# chaves.net
KiCad netlist of a schematic drawn in Altium Designer
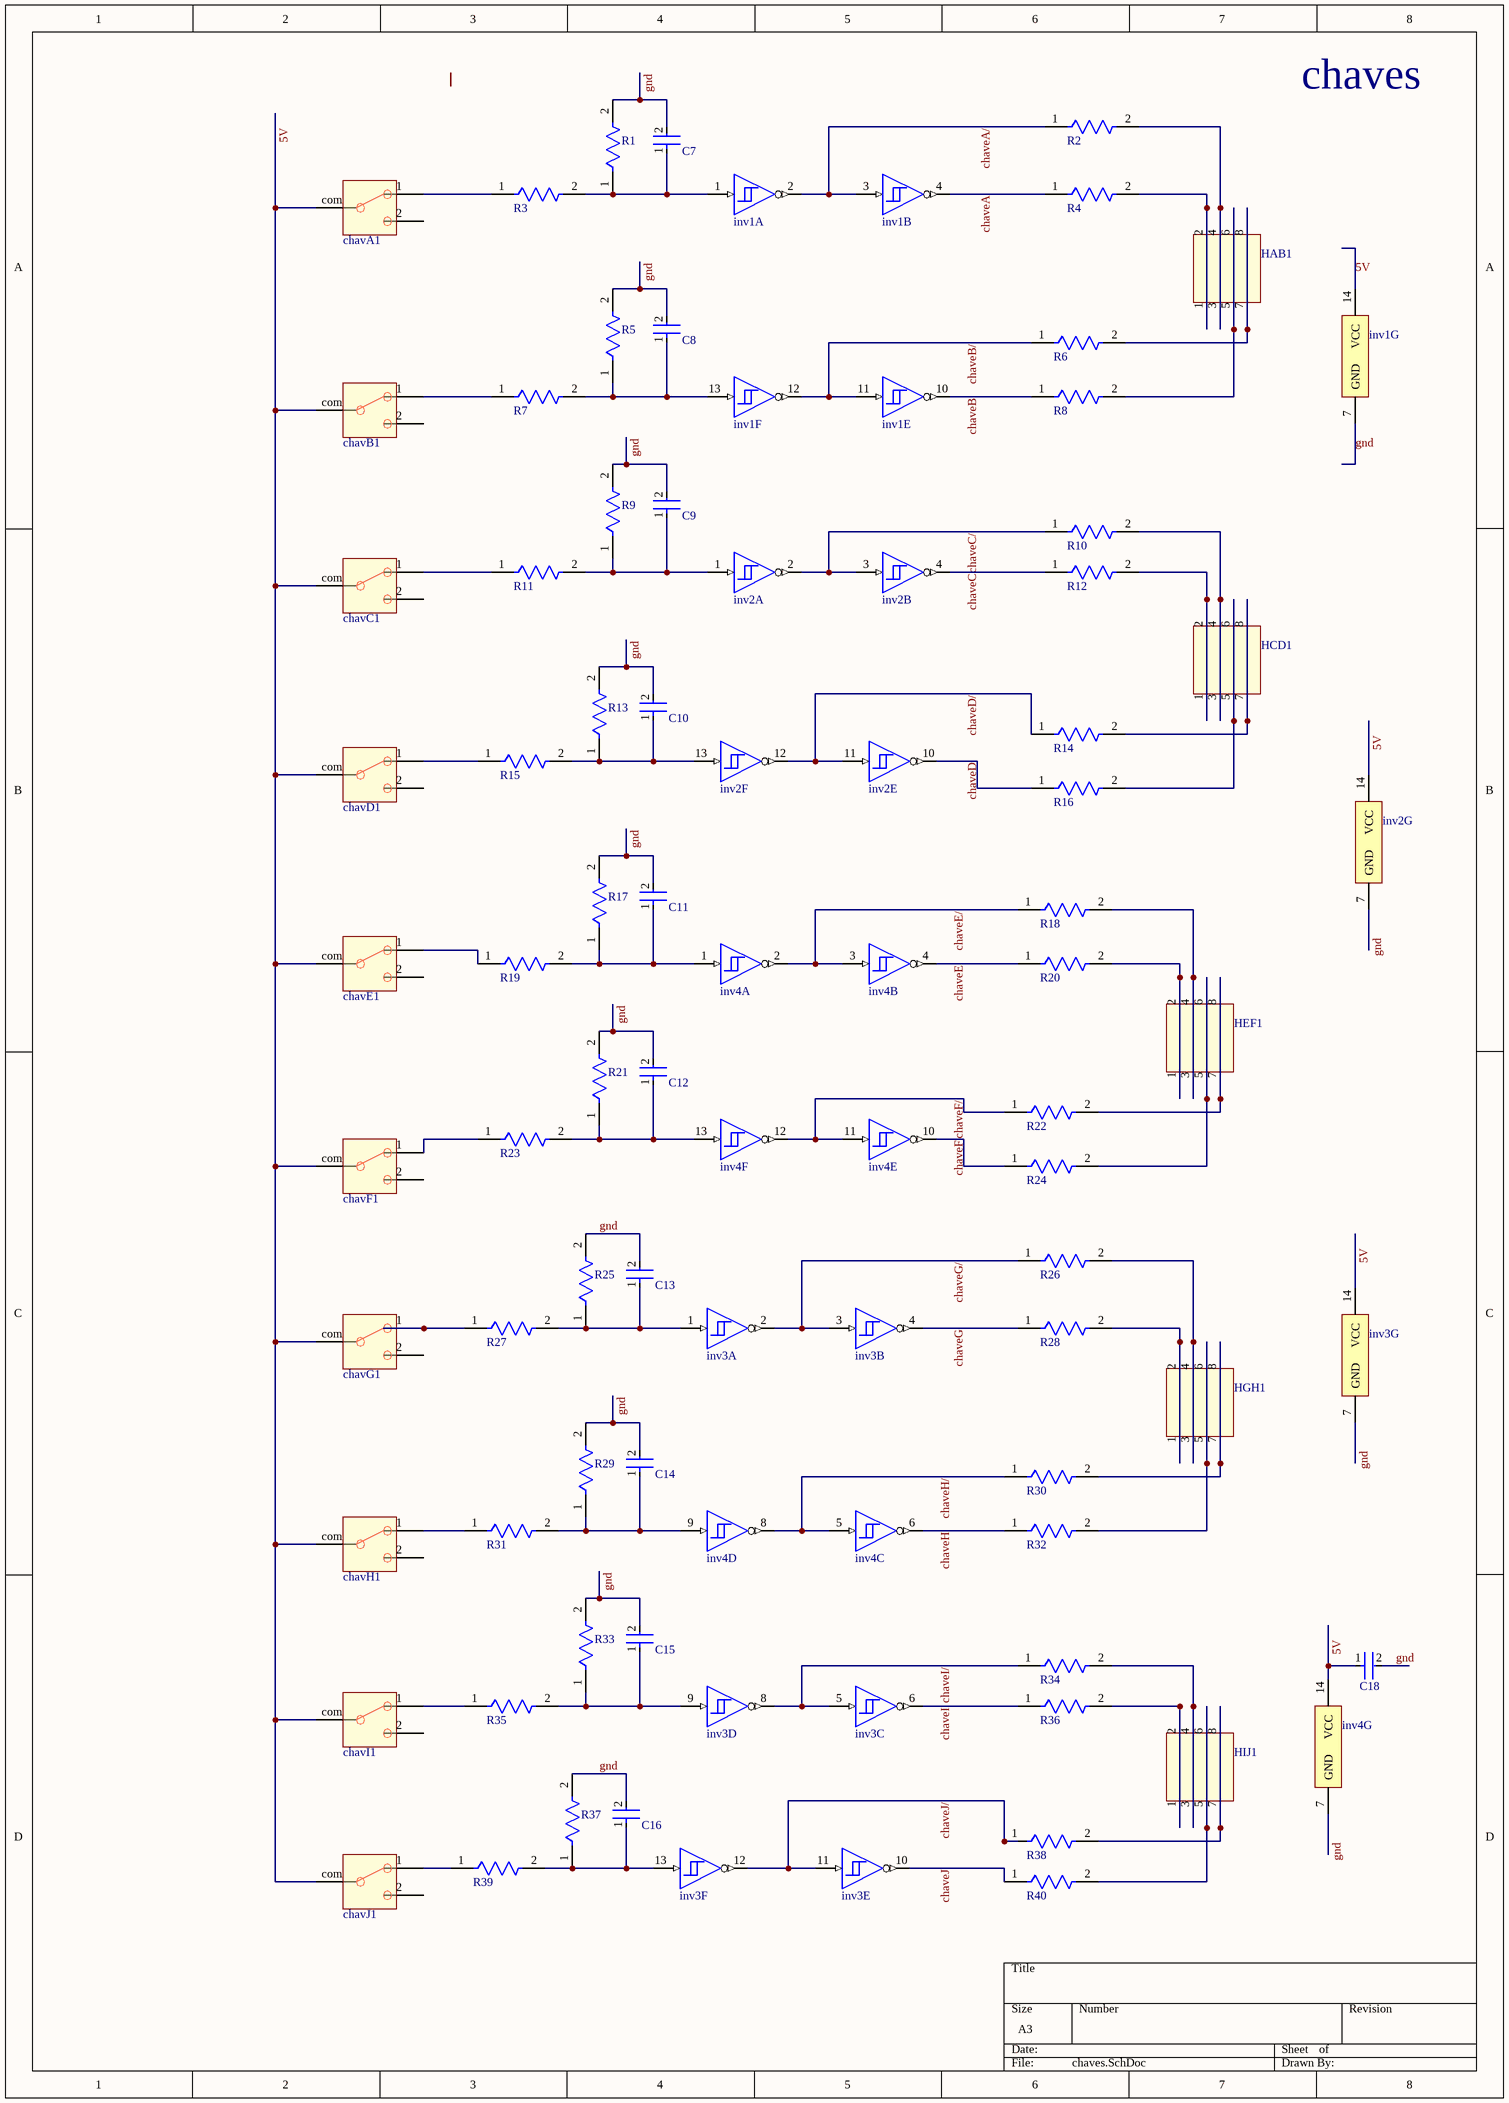
[diagram p0: chaves.SchDoc]

(export (version "E")
  (design (tool "Eeschema 10.0.6"))
  (components
    (comp (ref "C7")
      (value "RCER71H335K3K1H03B")
      (footprint "FP-RCE3M1-MFG")
      (description "Cap Ceramic 3.3uF 50V X7R ±10% Radial 5mm +125°C Automotive Ammo Pack")
      (fields (field (name "TOLERANCE") "10%"))
      (libsource (lib "Altium Content Vault") (part "02cd4be3c70576c341d710602a673aa"))
    )
    (comp (ref "C8")
      (value "RCER71H335K3K1H03B")
      (footprint "FP-RCE3M1-MFG")
      (description "Cap Ceramic 3.3uF 50V X7R ±10% Radial 5mm +125°C Automotive Ammo Pack")
      (fields (field (name "TOLERANCE") "10%"))
      (libsource (lib "Altium Content Vault") (part "02cd4be3c70576c341d710602a673aa"))
    )
    (comp (ref "C9")
      (value "RCER71H335K3K1H03B")
      (footprint "FP-RCE3M1-MFG")
      (description "Cap Ceramic 3.3uF 50V X7R ±10% Radial 5mm +125°C Automotive Ammo Pack")
      (fields (field (name "TOLERANCE") "10%"))
      (libsource (lib "Altium Content Vault") (part "02cd4be3c70576c341d710602a673aa"))
    )
    (comp (ref "C10")
      (value "RCER71H335K3K1H03B")
      (footprint "FP-RCE3M1-MFG")
      (description "Cap Ceramic 3.3uF 50V X7R ±10% Radial 5mm +125°C Automotive Ammo Pack")
      (fields (field (name "TOLERANCE") "10%"))
      (libsource (lib "Altium Content Vault") (part "02cd4be3c70576c341d710602a673aa"))
    )
    (comp (ref "C11")
      (value "RCER71H335K3K1H03B")
      (footprint "FP-RCE3M1-MFG")
      (description "Cap Ceramic 3.3uF 50V X7R ±10% Radial 5mm +125°C Automotive Ammo Pack")
      (fields (field (name "TOLERANCE") "10%"))
      (libsource (lib "Altium Content Vault") (part "02cd4be3c70576c341d710602a673aa"))
    )
    (comp (ref "C12")
      (value "RCER71H335K3K1H03B")
      (footprint "FP-RCE3M1-MFG")
      (description "Cap Ceramic 3.3uF 50V X7R ±10% Radial 5mm +125°C Automotive Ammo Pack")
      (fields (field (name "TOLERANCE") "10%"))
      (libsource (lib "Altium Content Vault") (part "02cd4be3c70576c341d710602a673aa"))
    )
    (comp (ref "C13")
      (value "RCER71H335K3K1H03B")
      (footprint "FP-RCE3M1-MFG")
      (description "Cap Ceramic 3.3uF 50V X7R ±10% Radial 5mm +125°C Automotive Ammo Pack")
      (fields (field (name "TOLERANCE") "10%"))
      (libsource (lib "Altium Content Vault") (part "02cd4be3c70576c341d710602a673aa"))
    )
    (comp (ref "C14")
      (value "RCER71H335K3K1H03B")
      (footprint "FP-RCE3M1-MFG")
      (description "Cap Ceramic 3.3uF 50V X7R ±10% Radial 5mm +125°C Automotive Ammo Pack")
      (fields (field (name "TOLERANCE") "10%"))
      (libsource (lib "Altium Content Vault") (part "02cd4be3c70576c341d710602a673aa"))
    )
    (comp (ref "C15")
      (value "RCER71H335K3K1H03B")
      (footprint "FP-RCE3M1-MFG")
      (description "Cap Ceramic 3.3uF 50V X7R ±10% Radial 5mm +125°C Automotive Ammo Pack")
      (fields (field (name "TOLERANCE") "10%"))
      (libsource (lib "Altium Content Vault") (part "02cd4be3c70576c341d710602a673aa"))
    )
    (comp (ref "C16")
      (value "RCER71H335K3K1H03B")
      (footprint "FP-RCE3M1-MFG")
      (description "Cap Ceramic 3.3uF 50V X7R ±10% Radial 5mm +125°C Automotive Ammo Pack")
      (fields (field (name "TOLERANCE") "10%"))
      (libsource (lib "Altium Content Vault") (part "02cd4be3c70576c341d710602a673aa"))
    )
    (comp (ref "C18")
      (value "RCER71H335K3K1H03B")
      (footprint "FP-RCE3M1-MFG")
      (description "Cap Ceramic 3.3uF 50V X7R ±10% Radial 5mm +125°C Automotive Ammo Pack")
      (fields (field (name "TOLERANCE") "10%"))
      (libsource (lib "Altium Content Vault") (part "02cd4be3c70576c341d710602a673aa"))
    )
    (comp (ref "chavA1")
      (value "chave MTS-102")
      (footprint "MTS-102")
      (description "chave caso seja usadsada sendo encaixada")
      (libsource (lib "Schlib1") (part "MTS-102"))
    )
    (comp (ref "chavB1")
      (value "chave MTS-102")
      (footprint "MTS-102")
      (description "chave caso seja usadsada sendo encaixada")
      (libsource (lib "Schlib1") (part "MTS-102"))
    )
    (comp (ref "chavC1")
      (value "chave MTS-102")
      (footprint "MTS-102")
      (description "chave caso seja usadsada sendo encaixada")
      (libsource (lib "Schlib1") (part "MTS-102"))
    )
    (comp (ref "chavD1")
      (value "chave MTS-102")
      (footprint "MTS-102")
      (description "chave caso seja usadsada sendo encaixada")
      (libsource (lib "Schlib1") (part "MTS-102"))
    )
    (comp (ref "chavE1")
      (value "chave MTS-102")
      (footprint "MTS-102")
      (description "chave caso seja usadsada sendo encaixada")
      (libsource (lib "Schlib1") (part "MTS-102"))
    )
    (comp (ref "chavF1")
      (value "chave MTS-102")
      (footprint "MTS-102")
      (description "chave caso seja usadsada sendo encaixada")
      (libsource (lib "Schlib1") (part "MTS-102"))
    )
    (comp (ref "chavG1")
      (value "chave MTS-102")
      (footprint "MTS-102")
      (description "chave caso seja usadsada sendo encaixada")
      (libsource (lib "Schlib1") (part "MTS-102"))
    )
    (comp (ref "chavH1")
      (value "chave MTS-102")
      (footprint "MTS-102")
      (description "chave caso seja usadsada sendo encaixada")
      (libsource (lib "Schlib1") (part "MTS-102"))
    )
    (comp (ref "chavI1")
      (value "chave MTS-102")
      (footprint "MTS-102")
      (description "chave caso seja usadsada sendo encaixada")
      (libsource (lib "Schlib1") (part "MTS-102"))
    )
    (comp (ref "chavJ1")
      (value "chave MTS-102")
      (footprint "MTS-102")
      (description "chave caso seja usadsada sendo encaixada")
      (libsource (lib "Schlib1") (part "MTS-102"))
    )
    (comp (ref "HAB1")
      (value "header 2x4")
      (footprint "header 2x4")
      (description "header male 2x4")
      (libsource (lib "Schlib1") (part "header 2x4"))
    )
    (comp (ref "HCD1")
      (value "header 2x4")
      (footprint "header 2x4")
      (description "header male 2x4")
      (libsource (lib "Schlib1") (part "header 2x4"))
    )
    (comp (ref "HEF1")
      (value "header 2x4")
      (footprint "header 2x4")
      (description "header male 2x4")
      (libsource (lib "Schlib1") (part "header 2x4"))
    )
    (comp (ref "HGH1")
      (value "header 2x4")
      (footprint "header 2x4")
      (description "header male 2x4")
      (libsource (lib "Schlib1") (part "header 2x4"))
    )
    (comp (ref "HIJ1")
      (value "header 2x4")
      (footprint "header 2x4")
      (description "header male 2x4")
      (libsource (lib "Schlib1") (part "header 2x4"))
    )
    (comp (ref "inv1")
      (value "SN74HC14N")
      (footprint "N0014A")
      (description "Hex Schmitt-Trigger Inverters, N0014A, TUBE")
      (fields
        (field (name "MANUFACTURER") "Texas Instruments")
        (field (name "GENERIC PART NUMBER") "SN74HC14")
      )
      (libsource (lib "Altium Content Vault") (part "TI-CD_SNX4XXXXXX4X_19A-14-SCHMITT"))
    )
    (comp (ref "inv2")
      (value "SN74HC14N")
      (footprint "N0014A")
      (description "Hex Schmitt-Trigger Inverters, N0014A, TUBE")
      (fields
        (field (name "MANUFACTURER") "Texas Instruments")
        (field (name "GENERIC PART NUMBER") "SN74HC14")
      )
      (libsource (lib "Altium Content Vault") (part "TI-CD_SNX4XXXXXX4X_19A-14-SCHMITT"))
    )
    (comp (ref "inv3")
      (value "SN74HC14N")
      (footprint "N0014A")
      (description "Hex Schmitt-Trigger Inverters, N0014A, TUBE")
      (fields
        (field (name "MANUFACTURER") "Texas Instruments")
        (field (name "GENERIC PART NUMBER") "SN74HC14")
      )
      (libsource (lib "Altium Content Vault") (part "TI-CD_SNX4XXXXXX4X_19A-14-SCHMITT"))
    )
    (comp (ref "inv4")
      (value "SN74HC14N")
      (footprint "N0014A")
      (description "Hex Schmitt-Trigger Inverters, N0014A, TUBE")
      (fields
        (field (name "MANUFACTURER") "Texas Instruments")
        (field (name "GENERIC PART NUMBER") "SN74HC14")
      )
      (libsource (lib "Altium Content Vault") (part "TI-CD_SNX4XXXXXX4X_19A-14-SCHMITT"))
    )
    (comp (ref "R1")
      (value "MRS16000C2002FCT00")
      (footprint "FP-MRS1600-MFG")
      (description "RES 20K OHM 0.4W 1% AXIAL")
      (fields (field (name "TOLERANCE") "1%"))
      (libsource (lib "Altium Content Vault") (part "1029c3af85768c4190bb7ad29bc67b5"))
    )
    (comp (ref "R2")
      (value "MRS16000C2002FCT00")
      (footprint "FP-MRS1600-MFG")
      (description "RES 20K OHM 0.4W 1% AXIAL")
      (fields (field (name "TOLERANCE") "1%"))
      (libsource (lib "Altium Content Vault") (part "1029c3af85768c4190bb7ad29bc67b5"))
    )
    (comp (ref "R3")
      (value "MRS16000C2002FCT00")
      (footprint "FP-MRS1600-MFG")
      (description "RES 20K OHM 0.4W 1% AXIAL")
      (fields (field (name "TOLERANCE") "1%"))
      (libsource (lib "Altium Content Vault") (part "1029c3af85768c4190bb7ad29bc67b5"))
    )
    (comp (ref "R4")
      (value "MRS16000C2002FCT00")
      (footprint "FP-MRS1600-MFG")
      (description "RES 20K OHM 0.4W 1% AXIAL")
      (fields (field (name "TOLERANCE") "1%"))
      (libsource (lib "Altium Content Vault") (part "1029c3af85768c4190bb7ad29bc67b5"))
    )
    (comp (ref "R5")
      (value "MRS16000C2002FCT00")
      (footprint "FP-MRS1600-MFG")
      (description "RES 20K OHM 0.4W 1% AXIAL")
      (fields (field (name "TOLERANCE") "1%"))
      (libsource (lib "Altium Content Vault") (part "1029c3af85768c4190bb7ad29bc67b5"))
    )
    (comp (ref "R6")
      (value "MRS16000C2002FCT00")
      (footprint "FP-MRS1600-MFG")
      (description "RES 20K OHM 0.4W 1% AXIAL")
      (fields (field (name "TOLERANCE") "1%"))
      (libsource (lib "Altium Content Vault") (part "1029c3af85768c4190bb7ad29bc67b5"))
    )
    (comp (ref "R7")
      (value "MRS16000C2002FCT00")
      (footprint "FP-MRS1600-MFG")
      (description "RES 20K OHM 0.4W 1% AXIAL")
      (fields (field (name "TOLERANCE") "1%"))
      (libsource (lib "Altium Content Vault") (part "1029c3af85768c4190bb7ad29bc67b5"))
    )
    (comp (ref "R8")
      (value "MRS16000C2002FCT00")
      (footprint "FP-MRS1600-MFG")
      (description "RES 20K OHM 0.4W 1% AXIAL")
      (fields (field (name "TOLERANCE") "1%"))
      (libsource (lib "Altium Content Vault") (part "1029c3af85768c4190bb7ad29bc67b5"))
    )
    (comp (ref "R9")
      (value "MRS16000C2002FCT00")
      (footprint "FP-MRS1600-MFG")
      (description "RES 20K OHM 0.4W 1% AXIAL")
      (fields (field (name "TOLERANCE") "1%"))
      (libsource (lib "Altium Content Vault") (part "1029c3af85768c4190bb7ad29bc67b5"))
    )
    (comp (ref "R10")
      (value "MRS16000C2002FCT00")
      (footprint "FP-MRS1600-MFG")
      (description "RES 20K OHM 0.4W 1% AXIAL")
      (fields (field (name "TOLERANCE") "1%"))
      (libsource (lib "Altium Content Vault") (part "1029c3af85768c4190bb7ad29bc67b5"))
    )
    (comp (ref "R11")
      (value "MRS16000C2002FCT00")
      (footprint "FP-MRS1600-MFG")
      (description "RES 20K OHM 0.4W 1% AXIAL")
      (fields (field (name "TOLERANCE") "1%"))
      (libsource (lib "Altium Content Vault") (part "1029c3af85768c4190bb7ad29bc67b5"))
    )
    (comp (ref "R12")
      (value "MRS16000C2002FCT00")
      (footprint "FP-MRS1600-MFG")
      (description "RES 20K OHM 0.4W 1% AXIAL")
      (fields (field (name "TOLERANCE") "1%"))
      (libsource (lib "Altium Content Vault") (part "1029c3af85768c4190bb7ad29bc67b5"))
    )
    (comp (ref "R13")
      (value "MRS16000C2002FCT00")
      (footprint "FP-MRS1600-MFG")
      (description "RES 20K OHM 0.4W 1% AXIAL")
      (fields (field (name "TOLERANCE") "1%"))
      (libsource (lib "Altium Content Vault") (part "1029c3af85768c4190bb7ad29bc67b5"))
    )
    (comp (ref "R14")
      (value "MRS16000C2002FCT00")
      (footprint "FP-MRS1600-MFG")
      (description "RES 20K OHM 0.4W 1% AXIAL")
      (fields (field (name "TOLERANCE") "1%"))
      (libsource (lib "Altium Content Vault") (part "1029c3af85768c4190bb7ad29bc67b5"))
    )
    (comp (ref "R15")
      (value "MRS16000C2002FCT00")
      (footprint "FP-MRS1600-MFG")
      (description "RES 20K OHM 0.4W 1% AXIAL")
      (fields (field (name "TOLERANCE") "1%"))
      (libsource (lib "Altium Content Vault") (part "1029c3af85768c4190bb7ad29bc67b5"))
    )
    (comp (ref "R16")
      (value "MRS16000C2002FCT00")
      (footprint "FP-MRS1600-MFG")
      (description "RES 20K OHM 0.4W 1% AXIAL")
      (fields (field (name "TOLERANCE") "1%"))
      (libsource (lib "Altium Content Vault") (part "1029c3af85768c4190bb7ad29bc67b5"))
    )
    (comp (ref "R17")
      (value "MRS16000C2002FCT00")
      (footprint "FP-MRS1600-MFG")
      (description "RES 20K OHM 0.4W 1% AXIAL")
      (fields (field (name "TOLERANCE") "1%"))
      (libsource (lib "Altium Content Vault") (part "1029c3af85768c4190bb7ad29bc67b5"))
    )
    (comp (ref "R18")
      (value "MRS16000C2002FCT00")
      (footprint "FP-MRS1600-MFG")
      (description "RES 20K OHM 0.4W 1% AXIAL")
      (fields (field (name "TOLERANCE") "1%"))
      (libsource (lib "Altium Content Vault") (part "1029c3af85768c4190bb7ad29bc67b5"))
    )
    (comp (ref "R19")
      (value "MRS16000C2002FCT00")
      (footprint "FP-MRS1600-MFG")
      (description "RES 20K OHM 0.4W 1% AXIAL")
      (fields (field (name "TOLERANCE") "1%"))
      (libsource (lib "Altium Content Vault") (part "1029c3af85768c4190bb7ad29bc67b5"))
    )
    (comp (ref "R20")
      (value "MRS16000C2002FCT00")
      (footprint "FP-MRS1600-MFG")
      (description "RES 20K OHM 0.4W 1% AXIAL")
      (fields (field (name "TOLERANCE") "1%"))
      (libsource (lib "Altium Content Vault") (part "1029c3af85768c4190bb7ad29bc67b5"))
    )
    (comp (ref "R21")
      (value "MRS16000C2002FCT00")
      (footprint "FP-MRS1600-MFG")
      (description "RES 20K OHM 0.4W 1% AXIAL")
      (fields (field (name "TOLERANCE") "1%"))
      (libsource (lib "Altium Content Vault") (part "1029c3af85768c4190bb7ad29bc67b5"))
    )
    (comp (ref "R22")
      (value "MRS16000C2002FCT00")
      (footprint "FP-MRS1600-MFG")
      (description "RES 20K OHM 0.4W 1% AXIAL")
      (fields (field (name "TOLERANCE") "1%"))
      (libsource (lib "Altium Content Vault") (part "1029c3af85768c4190bb7ad29bc67b5"))
    )
    (comp (ref "R23")
      (value "MRS16000C2002FCT00")
      (footprint "FP-MRS1600-MFG")
      (description "RES 20K OHM 0.4W 1% AXIAL")
      (fields (field (name "TOLERANCE") "1%"))
      (libsource (lib "Altium Content Vault") (part "1029c3af85768c4190bb7ad29bc67b5"))
    )
    (comp (ref "R24")
      (value "MRS16000C2002FCT00")
      (footprint "FP-MRS1600-MFG")
      (description "RES 20K OHM 0.4W 1% AXIAL")
      (fields (field (name "TOLERANCE") "1%"))
      (libsource (lib "Altium Content Vault") (part "1029c3af85768c4190bb7ad29bc67b5"))
    )
    (comp (ref "R25")
      (value "MRS16000C2002FCT00")
      (footprint "FP-MRS1600-MFG")
      (description "RES 20K OHM 0.4W 1% AXIAL")
      (fields (field (name "TOLERANCE") "1%"))
      (libsource (lib "Altium Content Vault") (part "1029c3af85768c4190bb7ad29bc67b5"))
    )
    (comp (ref "R26")
      (value "MRS16000C2002FCT00")
      (footprint "FP-MRS1600-MFG")
      (description "RES 20K OHM 0.4W 1% AXIAL")
      (fields (field (name "TOLERANCE") "1%"))
      (libsource (lib "Altium Content Vault") (part "1029c3af85768c4190bb7ad29bc67b5"))
    )
    (comp (ref "R27")
      (value "MRS16000C2002FCT00")
      (footprint "FP-MRS1600-MFG")
      (description "RES 20K OHM 0.4W 1% AXIAL")
      (fields (field (name "TOLERANCE") "1%"))
      (libsource (lib "Altium Content Vault") (part "1029c3af85768c4190bb7ad29bc67b5"))
    )
    (comp (ref "R28")
      (value "MRS16000C2002FCT00")
      (footprint "FP-MRS1600-MFG")
      (description "RES 20K OHM 0.4W 1% AXIAL")
      (fields (field (name "TOLERANCE") "1%"))
      (libsource (lib "Altium Content Vault") (part "1029c3af85768c4190bb7ad29bc67b5"))
    )
    (comp (ref "R29")
      (value "MRS16000C2002FCT00")
      (footprint "FP-MRS1600-MFG")
      (description "RES 20K OHM 0.4W 1% AXIAL")
      (fields (field (name "TOLERANCE") "1%"))
      (libsource (lib "Altium Content Vault") (part "1029c3af85768c4190bb7ad29bc67b5"))
    )
    (comp (ref "R30")
      (value "MRS16000C2002FCT00")
      (footprint "FP-MRS1600-MFG")
      (description "RES 20K OHM 0.4W 1% AXIAL")
      (fields (field (name "TOLERANCE") "1%"))
      (libsource (lib "Altium Content Vault") (part "1029c3af85768c4190bb7ad29bc67b5"))
    )
    (comp (ref "R31")
      (value "MRS16000C2002FCT00")
      (footprint "FP-MRS1600-MFG")
      (description "RES 20K OHM 0.4W 1% AXIAL")
      (fields (field (name "TOLERANCE") "1%"))
      (libsource (lib "Altium Content Vault") (part "1029c3af85768c4190bb7ad29bc67b5"))
    )
    (comp (ref "R32")
      (value "MRS16000C2002FCT00")
      (footprint "FP-MRS1600-MFG")
      (description "RES 20K OHM 0.4W 1% AXIAL")
      (fields (field (name "TOLERANCE") "1%"))
      (libsource (lib "Altium Content Vault") (part "1029c3af85768c4190bb7ad29bc67b5"))
    )
    (comp (ref "R33")
      (value "MRS16000C2002FCT00")
      (footprint "FP-MRS1600-MFG")
      (description "RES 20K OHM 0.4W 1% AXIAL")
      (fields (field (name "TOLERANCE") "1%"))
      (libsource (lib "Altium Content Vault") (part "1029c3af85768c4190bb7ad29bc67b5"))
    )
    (comp (ref "R34")
      (value "MRS16000C2002FCT00")
      (footprint "FP-MRS1600-MFG")
      (description "RES 20K OHM 0.4W 1% AXIAL")
      (fields (field (name "TOLERANCE") "1%"))
      (libsource (lib "Altium Content Vault") (part "1029c3af85768c4190bb7ad29bc67b5"))
    )
    (comp (ref "R35")
      (value "MRS16000C2002FCT00")
      (footprint "FP-MRS1600-MFG")
      (description "RES 20K OHM 0.4W 1% AXIAL")
      (fields (field (name "TOLERANCE") "1%"))
      (libsource (lib "Altium Content Vault") (part "1029c3af85768c4190bb7ad29bc67b5"))
    )
    (comp (ref "R36")
      (value "MRS16000C2002FCT00")
      (footprint "FP-MRS1600-MFG")
      (description "RES 20K OHM 0.4W 1% AXIAL")
      (fields (field (name "TOLERANCE") "1%"))
      (libsource (lib "Altium Content Vault") (part "1029c3af85768c4190bb7ad29bc67b5"))
    )
    (comp (ref "R37")
      (value "MRS16000C2002FCT00")
      (footprint "FP-MRS1600-MFG")
      (description "RES 20K OHM 0.4W 1% AXIAL")
      (fields (field (name "TOLERANCE") "1%"))
      (libsource (lib "Altium Content Vault") (part "1029c3af85768c4190bb7ad29bc67b5"))
    )
    (comp (ref "R38")
      (value "MRS16000C2002FCT00")
      (footprint "FP-MRS1600-MFG")
      (description "RES 20K OHM 0.4W 1% AXIAL")
      (fields (field (name "TOLERANCE") "1%"))
      (libsource (lib "Altium Content Vault") (part "1029c3af85768c4190bb7ad29bc67b5"))
    )
    (comp (ref "R39")
      (value "MRS16000C2002FCT00")
      (footprint "FP-MRS1600-MFG")
      (description "RES 20K OHM 0.4W 1% AXIAL")
      (fields (field (name "TOLERANCE") "1%"))
      (libsource (lib "Altium Content Vault") (part "1029c3af85768c4190bb7ad29bc67b5"))
    )
    (comp (ref "R40")
      (value "MRS16000C2002FCT00")
      (footprint "FP-MRS1600-MFG")
      (description "RES 20K OHM 0.4W 1% AXIAL")
      (fields (field (name "TOLERANCE") "1%"))
      (libsource (lib "Altium Content Vault") (part "1029c3af85768c4190bb7ad29bc67b5"))
    )
  )
  (nets
    (net (code "1") (name "/5V") (class "Default")
      (node (ref "C18") (pin "1") (pinfunction "1_1") (pintype "passive"))
      (node (ref "chavA1") (pin "com") (pinfunction "3_com") (pintype "passive"))
      (node (ref "chavB1") (pin "com") (pinfunction "3_com") (pintype "passive"))
      (node (ref "chavC1") (pin "com") (pinfunction "3_com") (pintype "passive"))
      (node (ref "chavD1") (pin "com") (pinfunction "3_com") (pintype "passive"))
      (node (ref "chavE1") (pin "com") (pinfunction "3_com") (pintype "passive"))
      (node (ref "chavF1") (pin "com") (pinfunction "3_com") (pintype "passive"))
      (node (ref "chavG1") (pin "com") (pinfunction "3_com") (pintype "passive"))
      (node (ref "chavH1") (pin "com") (pinfunction "3_com") (pintype "passive"))
      (node (ref "chavI1") (pin "com") (pinfunction "3_com") (pintype "passive"))
      (node (ref "chavJ1") (pin "com") (pinfunction "3_com") (pintype "passive"))
      (node (ref "inv1") (pin "14") (pinfunction "VCC_14") (pintype "power_in"))
      (node (ref "inv2") (pin "14") (pinfunction "VCC_14") (pintype "power_in"))
      (node (ref "inv3") (pin "14") (pinfunction "VCC_14") (pintype "power_in"))
      (node (ref "inv4") (pin "14") (pinfunction "VCC_14") (pintype "power_in"))
    )
    (net (code "2") (name "/chaveA") (class "Default")
      (node (ref "R4") (pin "1") (pinfunction "1_1") (pintype "passive"))
      (node (ref "inv1") (pin "4") (pinfunction "~{2Y}_4") (pintype "output"))
    )
    (net (code "3") (name "/chaveA{slash}") (class "Default")
      (node (ref "R2") (pin "1") (pinfunction "1_1") (pintype "passive"))
      (node (ref "inv1") (pin "2") (pinfunction "~{1Y}_2") (pintype "output"))
      (node (ref "inv1") (pin "3") (pinfunction "2A_3") (pintype "input"))
    )
    (net (code "4") (name "/chaveB") (class "Default")
      (node (ref "R8") (pin "1") (pinfunction "1_1") (pintype "passive"))
      (node (ref "inv1") (pin "10") (pinfunction "~{5Y}_10") (pintype "output"))
    )
    (net (code "5") (name "/chaveB{slash}") (class "Default")
      (node (ref "R6") (pin "1") (pinfunction "1_1") (pintype "passive"))
      (node (ref "inv1") (pin "11") (pinfunction "5A_11") (pintype "input"))
      (node (ref "inv1") (pin "12") (pinfunction "~{6Y}_12") (pintype "output"))
    )
    (net (code "6") (name "/chaveC") (class "Default")
      (node (ref "R12") (pin "1") (pinfunction "1_1") (pintype "passive"))
      (node (ref "inv2") (pin "4") (pinfunction "~{2Y}_4") (pintype "output"))
    )
    (net (code "7") (name "/chaveC{slash}") (class "Default")
      (node (ref "R10") (pin "1") (pinfunction "1_1") (pintype "passive"))
      (node (ref "inv2") (pin "2") (pinfunction "~{1Y}_2") (pintype "output"))
      (node (ref "inv2") (pin "3") (pinfunction "2A_3") (pintype "input"))
    )
    (net (code "8") (name "/chaveD") (class "Default")
      (node (ref "R16") (pin "1") (pinfunction "1_1") (pintype "passive"))
      (node (ref "inv2") (pin "10") (pinfunction "~{5Y}_10") (pintype "output"))
    )
    (net (code "9") (name "/chaveD{slash}") (class "Default")
      (node (ref "R14") (pin "1") (pinfunction "1_1") (pintype "passive"))
      (node (ref "inv2") (pin "11") (pinfunction "5A_11") (pintype "input"))
      (node (ref "inv2") (pin "12") (pinfunction "~{6Y}_12") (pintype "output"))
    )
    (net (code "10") (name "/chaveE") (class "Default")
      (node (ref "R20") (pin "1") (pinfunction "1_1") (pintype "passive"))
      (node (ref "inv4") (pin "4") (pinfunction "~{2Y}_4") (pintype "output"))
    )
    (net (code "11") (name "/chaveE{slash}") (class "Default")
      (node (ref "R18") (pin "1") (pinfunction "1_1") (pintype "passive"))
      (node (ref "inv4") (pin "2") (pinfunction "~{1Y}_2") (pintype "output"))
      (node (ref "inv4") (pin "3") (pinfunction "2A_3") (pintype "input"))
    )
    (net (code "12") (name "/chaveF") (class "Default")
      (node (ref "R24") (pin "1") (pinfunction "1_1") (pintype "passive"))
      (node (ref "inv4") (pin "10") (pinfunction "~{5Y}_10") (pintype "output"))
    )
    (net (code "13") (name "/chaveF{slash}") (class "Default")
      (node (ref "R22") (pin "1") (pinfunction "1_1") (pintype "passive"))
      (node (ref "inv4") (pin "11") (pinfunction "5A_11") (pintype "input"))
      (node (ref "inv4") (pin "12") (pinfunction "~{6Y}_12") (pintype "output"))
    )
    (net (code "14") (name "/chaveG") (class "Default")
      (node (ref "R28") (pin "1") (pinfunction "1_1") (pintype "passive"))
      (node (ref "inv3") (pin "4") (pinfunction "~{2Y}_4") (pintype "output"))
    )
    (net (code "15") (name "/chaveG{slash}") (class "Default")
      (node (ref "R26") (pin "1") (pinfunction "1_1") (pintype "passive"))
      (node (ref "inv3") (pin "2") (pinfunction "~{1Y}_2") (pintype "output"))
      (node (ref "inv3") (pin "3") (pinfunction "2A_3") (pintype "input"))
    )
    (net (code "16") (name "/chaveH") (class "Default")
      (node (ref "R32") (pin "1") (pinfunction "1_1") (pintype "passive"))
      (node (ref "inv4") (pin "6") (pinfunction "~{3Y}_6") (pintype "output"))
    )
    (net (code "17") (name "/chaveH{slash}") (class "Default")
      (node (ref "R30") (pin "1") (pinfunction "1_1") (pintype "passive"))
      (node (ref "inv4") (pin "5") (pinfunction "3A_5") (pintype "input"))
      (node (ref "inv4") (pin "8") (pinfunction "~{4Y}_8") (pintype "output"))
    )
    (net (code "18") (name "/chaveI") (class "Default")
      (node (ref "R36") (pin "1") (pinfunction "1_1") (pintype "passive"))
      (node (ref "inv3") (pin "6") (pinfunction "~{3Y}_6") (pintype "output"))
    )
    (net (code "19") (name "/chaveI{slash}") (class "Default")
      (node (ref "R34") (pin "1") (pinfunction "1_1") (pintype "passive"))
      (node (ref "inv3") (pin "5") (pinfunction "3A_5") (pintype "input"))
      (node (ref "inv3") (pin "8") (pinfunction "~{4Y}_8") (pintype "output"))
    )
    (net (code "20") (name "/chaveJ") (class "Default")
      (node (ref "R40") (pin "1") (pinfunction "1_1") (pintype "passive"))
      (node (ref "inv3") (pin "10") (pinfunction "~{5Y}_10") (pintype "output"))
    )
    (net (code "21") (name "/chaveJ{slash}") (class "Default")
      (node (ref "R38") (pin "1") (pinfunction "1_1") (pintype "passive"))
      (node (ref "inv3") (pin "11") (pinfunction "5A_11") (pintype "input"))
      (node (ref "inv3") (pin "12") (pinfunction "~{6Y}_12") (pintype "output"))
    )
    (net (code "22") (name "/gnd") (class "Default")
      (node (ref "C10") (pin "2") (pinfunction "2_2") (pintype "passive"))
      (node (ref "C11") (pin "2") (pinfunction "2_2") (pintype "passive"))
      (node (ref "C12") (pin "2") (pinfunction "2_2") (pintype "passive"))
      (node (ref "C13") (pin "2") (pinfunction "2_2") (pintype "passive"))
      (node (ref "C14") (pin "2") (pinfunction "2_2") (pintype "passive"))
      (node (ref "C15") (pin "2") (pinfunction "2_2") (pintype "passive"))
      (node (ref "C16") (pin "2") (pinfunction "2_2") (pintype "passive"))
      (node (ref "C18") (pin "2") (pinfunction "2_2") (pintype "passive"))
      (node (ref "C7") (pin "2") (pinfunction "2_2") (pintype "passive"))
      (node (ref "C8") (pin "2") (pinfunction "2_2") (pintype "passive"))
      (node (ref "C9") (pin "2") (pinfunction "2_2") (pintype "passive"))
      (node (ref "R1") (pin "2") (pinfunction "2_2") (pintype "passive"))
      (node (ref "R13") (pin "2") (pinfunction "2_2") (pintype "passive"))
      (node (ref "R17") (pin "2") (pinfunction "2_2") (pintype "passive"))
      (node (ref "R21") (pin "2") (pinfunction "2_2") (pintype "passive"))
      (node (ref "R25") (pin "2") (pinfunction "2_2") (pintype "passive"))
      (node (ref "R29") (pin "2") (pinfunction "2_2") (pintype "passive"))
      (node (ref "R33") (pin "2") (pinfunction "2_2") (pintype "passive"))
      (node (ref "R37") (pin "2") (pinfunction "2_2") (pintype "passive"))
      (node (ref "R5") (pin "2") (pinfunction "2_2") (pintype "passive"))
      (node (ref "R9") (pin "2") (pinfunction "2_2") (pintype "passive"))
      (node (ref "inv1") (pin "7") (pinfunction "GND_7") (pintype "power_in"))
      (node (ref "inv2") (pin "7") (pinfunction "GND_7") (pintype "power_in"))
      (node (ref "inv3") (pin "7") (pinfunction "GND_7") (pintype "power_in"))
      (node (ref "inv4") (pin "7") (pinfunction "GND_7") (pintype "power_in"))
    )
    (net (code "23") (name "Net-(HAB1-Pad1)") (class "Default")
      (node (ref "HAB1") (pin "1") (pinfunction "1_1") (pintype "passive"))
      (node (ref "HAB1") (pin "2") (pinfunction "2_2") (pintype "passive"))
      (node (ref "R4") (pin "2") (pinfunction "2_2") (pintype "passive"))
    )
    (net (code "24") (name "Net-(HAB1-Pad3)") (class "Default")
      (node (ref "HAB1") (pin "3") (pinfunction "3_3") (pintype "passive"))
      (node (ref "HAB1") (pin "4") (pinfunction "4_4") (pintype "passive"))
      (node (ref "R2") (pin "2") (pinfunction "2_2") (pintype "passive"))
    )
    (net (code "25") (name "Net-(HAB1-Pad5)") (class "Default")
      (node (ref "HAB1") (pin "5") (pinfunction "5_5") (pintype "passive"))
      (node (ref "HAB1") (pin "6") (pinfunction "6_6") (pintype "passive"))
      (node (ref "R8") (pin "2") (pinfunction "2_2") (pintype "passive"))
    )
    (net (code "26") (name "Net-(HAB1-Pad7)") (class "Default")
      (node (ref "HAB1") (pin "7") (pinfunction "7_7") (pintype "passive"))
      (node (ref "HAB1") (pin "8") (pinfunction "8_8") (pintype "passive"))
      (node (ref "R6") (pin "2") (pinfunction "2_2") (pintype "passive"))
    )
    (net (code "27") (name "Net-(HCD1-Pad1)") (class "Default")
      (node (ref "HCD1") (pin "1") (pinfunction "1_1") (pintype "passive"))
      (node (ref "HCD1") (pin "2") (pinfunction "2_2") (pintype "passive"))
      (node (ref "R12") (pin "2") (pinfunction "2_2") (pintype "passive"))
    )
    (net (code "28") (name "Net-(HCD1-Pad3)") (class "Default")
      (node (ref "HCD1") (pin "3") (pinfunction "3_3") (pintype "passive"))
      (node (ref "HCD1") (pin "4") (pinfunction "4_4") (pintype "passive"))
      (node (ref "R10") (pin "2") (pinfunction "2_2") (pintype "passive"))
    )
    (net (code "29") (name "Net-(HCD1-Pad5)") (class "Default")
      (node (ref "HCD1") (pin "5") (pinfunction "5_5") (pintype "passive"))
      (node (ref "HCD1") (pin "6") (pinfunction "6_6") (pintype "passive"))
      (node (ref "R16") (pin "2") (pinfunction "2_2") (pintype "passive"))
    )
    (net (code "30") (name "Net-(HCD1-Pad7)") (class "Default")
      (node (ref "HCD1") (pin "7") (pinfunction "7_7") (pintype "passive"))
      (node (ref "HCD1") (pin "8") (pinfunction "8_8") (pintype "passive"))
      (node (ref "R14") (pin "2") (pinfunction "2_2") (pintype "passive"))
    )
    (net (code "31") (name "Net-(HEF1-Pad1)") (class "Default")
      (node (ref "HEF1") (pin "1") (pinfunction "1_1") (pintype "passive"))
      (node (ref "HEF1") (pin "2") (pinfunction "2_2") (pintype "passive"))
      (node (ref "R20") (pin "2") (pinfunction "2_2") (pintype "passive"))
    )
    (net (code "32") (name "Net-(HEF1-Pad3)") (class "Default")
      (node (ref "HEF1") (pin "3") (pinfunction "3_3") (pintype "passive"))
      (node (ref "HEF1") (pin "4") (pinfunction "4_4") (pintype "passive"))
      (node (ref "R18") (pin "2") (pinfunction "2_2") (pintype "passive"))
    )
    (net (code "33") (name "Net-(HEF1-Pad5)") (class "Default")
      (node (ref "HEF1") (pin "5") (pinfunction "5_5") (pintype "passive"))
      (node (ref "HEF1") (pin "6") (pinfunction "6_6") (pintype "passive"))
      (node (ref "R24") (pin "2") (pinfunction "2_2") (pintype "passive"))
    )
    (net (code "34") (name "Net-(HEF1-Pad7)") (class "Default")
      (node (ref "HEF1") (pin "7") (pinfunction "7_7") (pintype "passive"))
      (node (ref "HEF1") (pin "8") (pinfunction "8_8") (pintype "passive"))
      (node (ref "R22") (pin "2") (pinfunction "2_2") (pintype "passive"))
    )
    (net (code "35") (name "Net-(HGH1-Pad1)") (class "Default")
      (node (ref "HGH1") (pin "1") (pinfunction "1_1") (pintype "passive"))
      (node (ref "HGH1") (pin "2") (pinfunction "2_2") (pintype "passive"))
      (node (ref "R28") (pin "2") (pinfunction "2_2") (pintype "passive"))
    )
    (net (code "36") (name "Net-(HGH1-Pad3)") (class "Default")
      (node (ref "HGH1") (pin "3") (pinfunction "3_3") (pintype "passive"))
      (node (ref "HGH1") (pin "4") (pinfunction "4_4") (pintype "passive"))
      (node (ref "R26") (pin "2") (pinfunction "2_2") (pintype "passive"))
    )
    (net (code "37") (name "Net-(HGH1-Pad5)") (class "Default")
      (node (ref "HGH1") (pin "5") (pinfunction "5_5") (pintype "passive"))
      (node (ref "HGH1") (pin "6") (pinfunction "6_6") (pintype "passive"))
      (node (ref "R32") (pin "2") (pinfunction "2_2") (pintype "passive"))
    )
    (net (code "38") (name "Net-(HGH1-Pad7)") (class "Default")
      (node (ref "HGH1") (pin "7") (pinfunction "7_7") (pintype "passive"))
      (node (ref "HGH1") (pin "8") (pinfunction "8_8") (pintype "passive"))
      (node (ref "R30") (pin "2") (pinfunction "2_2") (pintype "passive"))
    )
    (net (code "39") (name "Net-(HIJ1-Pad1)") (class "Default")
      (node (ref "HIJ1") (pin "1") (pinfunction "1_1") (pintype "passive"))
      (node (ref "HIJ1") (pin "2") (pinfunction "2_2") (pintype "passive"))
      (node (ref "R36") (pin "2") (pinfunction "2_2") (pintype "passive"))
    )
    (net (code "40") (name "Net-(HIJ1-Pad3)") (class "Default")
      (node (ref "HIJ1") (pin "3") (pinfunction "3_3") (pintype "passive"))
      (node (ref "HIJ1") (pin "4") (pinfunction "4_4") (pintype "passive"))
      (node (ref "R34") (pin "2") (pinfunction "2_2") (pintype "passive"))
    )
    (net (code "41") (name "Net-(HIJ1-Pad5)") (class "Default")
      (node (ref "HIJ1") (pin "5") (pinfunction "5_5") (pintype "passive"))
      (node (ref "HIJ1") (pin "6") (pinfunction "6_6") (pintype "passive"))
      (node (ref "R40") (pin "2") (pinfunction "2_2") (pintype "passive"))
    )
    (net (code "42") (name "Net-(HIJ1-Pad7)") (class "Default")
      (node (ref "HIJ1") (pin "7") (pinfunction "7_7") (pintype "passive"))
      (node (ref "HIJ1") (pin "8") (pinfunction "8_8") (pintype "passive"))
      (node (ref "R38") (pin "2") (pinfunction "2_2") (pintype "passive"))
    )
    (net (code "43") (name "Net-(R3-Pad1)") (class "Default")
      (node (ref "R3") (pin "1") (pinfunction "1_1") (pintype "passive"))
      (node (ref "chavA1") (pin "1") (pinfunction "1_1") (pintype "passive"))
    )
    (net (code "44") (name "Net-(R7-Pad1)") (class "Default")
      (node (ref "R7") (pin "1") (pinfunction "1_1") (pintype "passive"))
      (node (ref "chavB1") (pin "1") (pinfunction "1_1") (pintype "passive"))
    )
    (net (code "45") (name "Net-(R11-Pad1)") (class "Default")
      (node (ref "R11") (pin "1") (pinfunction "1_1") (pintype "passive"))
      (node (ref "chavC1") (pin "1") (pinfunction "1_1") (pintype "passive"))
    )
    (net (code "46") (name "Net-(R15-Pad1)") (class "Default")
      (node (ref "R15") (pin "1") (pinfunction "1_1") (pintype "passive"))
      (node (ref "chavD1") (pin "1") (pinfunction "1_1") (pintype "passive"))
    )
    (net (code "47") (name "Net-(R19-Pad1)") (class "Default")
      (node (ref "R19") (pin "1") (pinfunction "1_1") (pintype "passive"))
      (node (ref "chavE1") (pin "1") (pinfunction "1_1") (pintype "passive"))
    )
    (net (code "48") (name "Net-(R23-Pad1)") (class "Default")
      (node (ref "R23") (pin "1") (pinfunction "1_1") (pintype "passive"))
      (node (ref "chavF1") (pin "1") (pinfunction "1_1") (pintype "passive"))
    )
    (net (code "49") (name "Net-(R27-Pad1)") (class "Default")
      (node (ref "R27") (pin "1") (pinfunction "1_1") (pintype "passive"))
      (node (ref "chavG1") (pin "1") (pinfunction "1_1") (pintype "passive"))
    )
    (net (code "50") (name "Net-(R31-Pad1)") (class "Default")
      (node (ref "R31") (pin "1") (pinfunction "1_1") (pintype "passive"))
      (node (ref "chavH1") (pin "1") (pinfunction "1_1") (pintype "passive"))
    )
    (net (code "51") (name "Net-(R35-Pad1)") (class "Default")
      (node (ref "R35") (pin "1") (pinfunction "1_1") (pintype "passive"))
      (node (ref "chavI1") (pin "1") (pinfunction "1_1") (pintype "passive"))
    )
    (net (code "52") (name "Net-(R39-Pad1)") (class "Default")
      (node (ref "R39") (pin "1") (pinfunction "1_1") (pintype "passive"))
      (node (ref "chavJ1") (pin "1") (pinfunction "1_1") (pintype "passive"))
    )
    (net (code "53") (name "Net-(inv1A-1A)") (class "Default")
      (node (ref "C7") (pin "1") (pinfunction "1_1") (pintype "passive"))
      (node (ref "R1") (pin "1") (pinfunction "1_1") (pintype "passive"))
      (node (ref "R3") (pin "2") (pinfunction "2_2") (pintype "passive"))
      (node (ref "inv1") (pin "1") (pinfunction "1A_1") (pintype "input"))
    )
    (net (code "54") (name "Net-(inv1F-6A)") (class "Default")
      (node (ref "C8") (pin "1") (pinfunction "1_1") (pintype "passive"))
      (node (ref "R5") (pin "1") (pinfunction "1_1") (pintype "passive"))
      (node (ref "R7") (pin "2") (pinfunction "2_2") (pintype "passive"))
      (node (ref "inv1") (pin "13") (pinfunction "6A_13") (pintype "input"))
    )
    (net (code "55") (name "Net-(inv2A-1A)") (class "Default")
      (node (ref "C9") (pin "1") (pinfunction "1_1") (pintype "passive"))
      (node (ref "R11") (pin "2") (pinfunction "2_2") (pintype "passive"))
      (node (ref "R9") (pin "1") (pinfunction "1_1") (pintype "passive"))
      (node (ref "inv2") (pin "1") (pinfunction "1A_1") (pintype "input"))
    )
    (net (code "56") (name "Net-(inv2F-6A)") (class "Default")
      (node (ref "C10") (pin "1") (pinfunction "1_1") (pintype "passive"))
      (node (ref "R13") (pin "1") (pinfunction "1_1") (pintype "passive"))
      (node (ref "R15") (pin "2") (pinfunction "2_2") (pintype "passive"))
      (node (ref "inv2") (pin "13") (pinfunction "6A_13") (pintype "input"))
    )
    (net (code "57") (name "Net-(inv3A-1A)") (class "Default")
      (node (ref "C13") (pin "1") (pinfunction "1_1") (pintype "passive"))
      (node (ref "R25") (pin "1") (pinfunction "1_1") (pintype "passive"))
      (node (ref "R27") (pin "2") (pinfunction "2_2") (pintype "passive"))
      (node (ref "inv3") (pin "1") (pinfunction "1A_1") (pintype "input"))
    )
    (net (code "58") (name "Net-(inv3D-4A)") (class "Default")
      (node (ref "C15") (pin "1") (pinfunction "1_1") (pintype "passive"))
      (node (ref "R33") (pin "1") (pinfunction "1_1") (pintype "passive"))
      (node (ref "R35") (pin "2") (pinfunction "2_2") (pintype "passive"))
      (node (ref "inv3") (pin "9") (pinfunction "4A_9") (pintype "input"))
    )
    (net (code "59") (name "Net-(inv3F-6A)") (class "Default")
      (node (ref "C16") (pin "1") (pinfunction "1_1") (pintype "passive"))
      (node (ref "R37") (pin "1") (pinfunction "1_1") (pintype "passive"))
      (node (ref "R39") (pin "2") (pinfunction "2_2") (pintype "passive"))
      (node (ref "inv3") (pin "13") (pinfunction "6A_13") (pintype "input"))
    )
    (net (code "60") (name "Net-(inv4A-1A)") (class "Default")
      (node (ref "C11") (pin "1") (pinfunction "1_1") (pintype "passive"))
      (node (ref "R17") (pin "1") (pinfunction "1_1") (pintype "passive"))
      (node (ref "R19") (pin "2") (pinfunction "2_2") (pintype "passive"))
      (node (ref "inv4") (pin "1") (pinfunction "1A_1") (pintype "input"))
    )
    (net (code "61") (name "Net-(inv4D-4A)") (class "Default")
      (node (ref "C14") (pin "1") (pinfunction "1_1") (pintype "passive"))
      (node (ref "R29") (pin "1") (pinfunction "1_1") (pintype "passive"))
      (node (ref "R31") (pin "2") (pinfunction "2_2") (pintype "passive"))
      (node (ref "inv4") (pin "9") (pinfunction "4A_9") (pintype "input"))
    )
    (net (code "62") (name "Net-(inv4F-6A)") (class "Default")
      (node (ref "C12") (pin "1") (pinfunction "1_1") (pintype "passive"))
      (node (ref "R21") (pin "1") (pinfunction "1_1") (pintype "passive"))
      (node (ref "R23") (pin "2") (pinfunction "2_2") (pintype "passive"))
      (node (ref "inv4") (pin "13") (pinfunction "6A_13") (pintype "input"))
    )
    (net (code "63") (name "unconnected-(chavA1-Pad2)") (class "Default")
      (node (ref "chavA1") (pin "2") (pinfunction "2_2") (pintype "passive"))
    )
    (net (code "64") (name "unconnected-(chavB1-Pad2)") (class "Default")
      (node (ref "chavB1") (pin "2") (pinfunction "2_2") (pintype "passive"))
    )
    (net (code "65") (name "unconnected-(chavC1-Pad2)") (class "Default")
      (node (ref "chavC1") (pin "2") (pinfunction "2_2") (pintype "passive"))
    )
    (net (code "66") (name "unconnected-(chavD1-Pad2)") (class "Default")
      (node (ref "chavD1") (pin "2") (pinfunction "2_2") (pintype "passive"))
    )
    (net (code "67") (name "unconnected-(chavE1-Pad2)") (class "Default")
      (node (ref "chavE1") (pin "2") (pinfunction "2_2") (pintype "passive"))
    )
    (net (code "68") (name "unconnected-(chavF1-Pad2)") (class "Default")
      (node (ref "chavF1") (pin "2") (pinfunction "2_2") (pintype "passive"))
    )
    (net (code "69") (name "unconnected-(chavG1-Pad2)") (class "Default")
      (node (ref "chavG1") (pin "2") (pinfunction "2_2") (pintype "passive"))
    )
    (net (code "70") (name "unconnected-(chavH1-Pad2)") (class "Default")
      (node (ref "chavH1") (pin "2") (pinfunction "2_2") (pintype "passive"))
    )
    (net (code "71") (name "unconnected-(chavI1-Pad2)") (class "Default")
      (node (ref "chavI1") (pin "2") (pinfunction "2_2") (pintype "passive"))
    )
    (net (code "72") (name "unconnected-(chavJ1-Pad2)") (class "Default")
      (node (ref "chavJ1") (pin "2") (pinfunction "2_2") (pintype "passive"))
    )
  )
)
